# M482SIDv2.net
KiCad netlist of a schematic drawn in EasyEDA
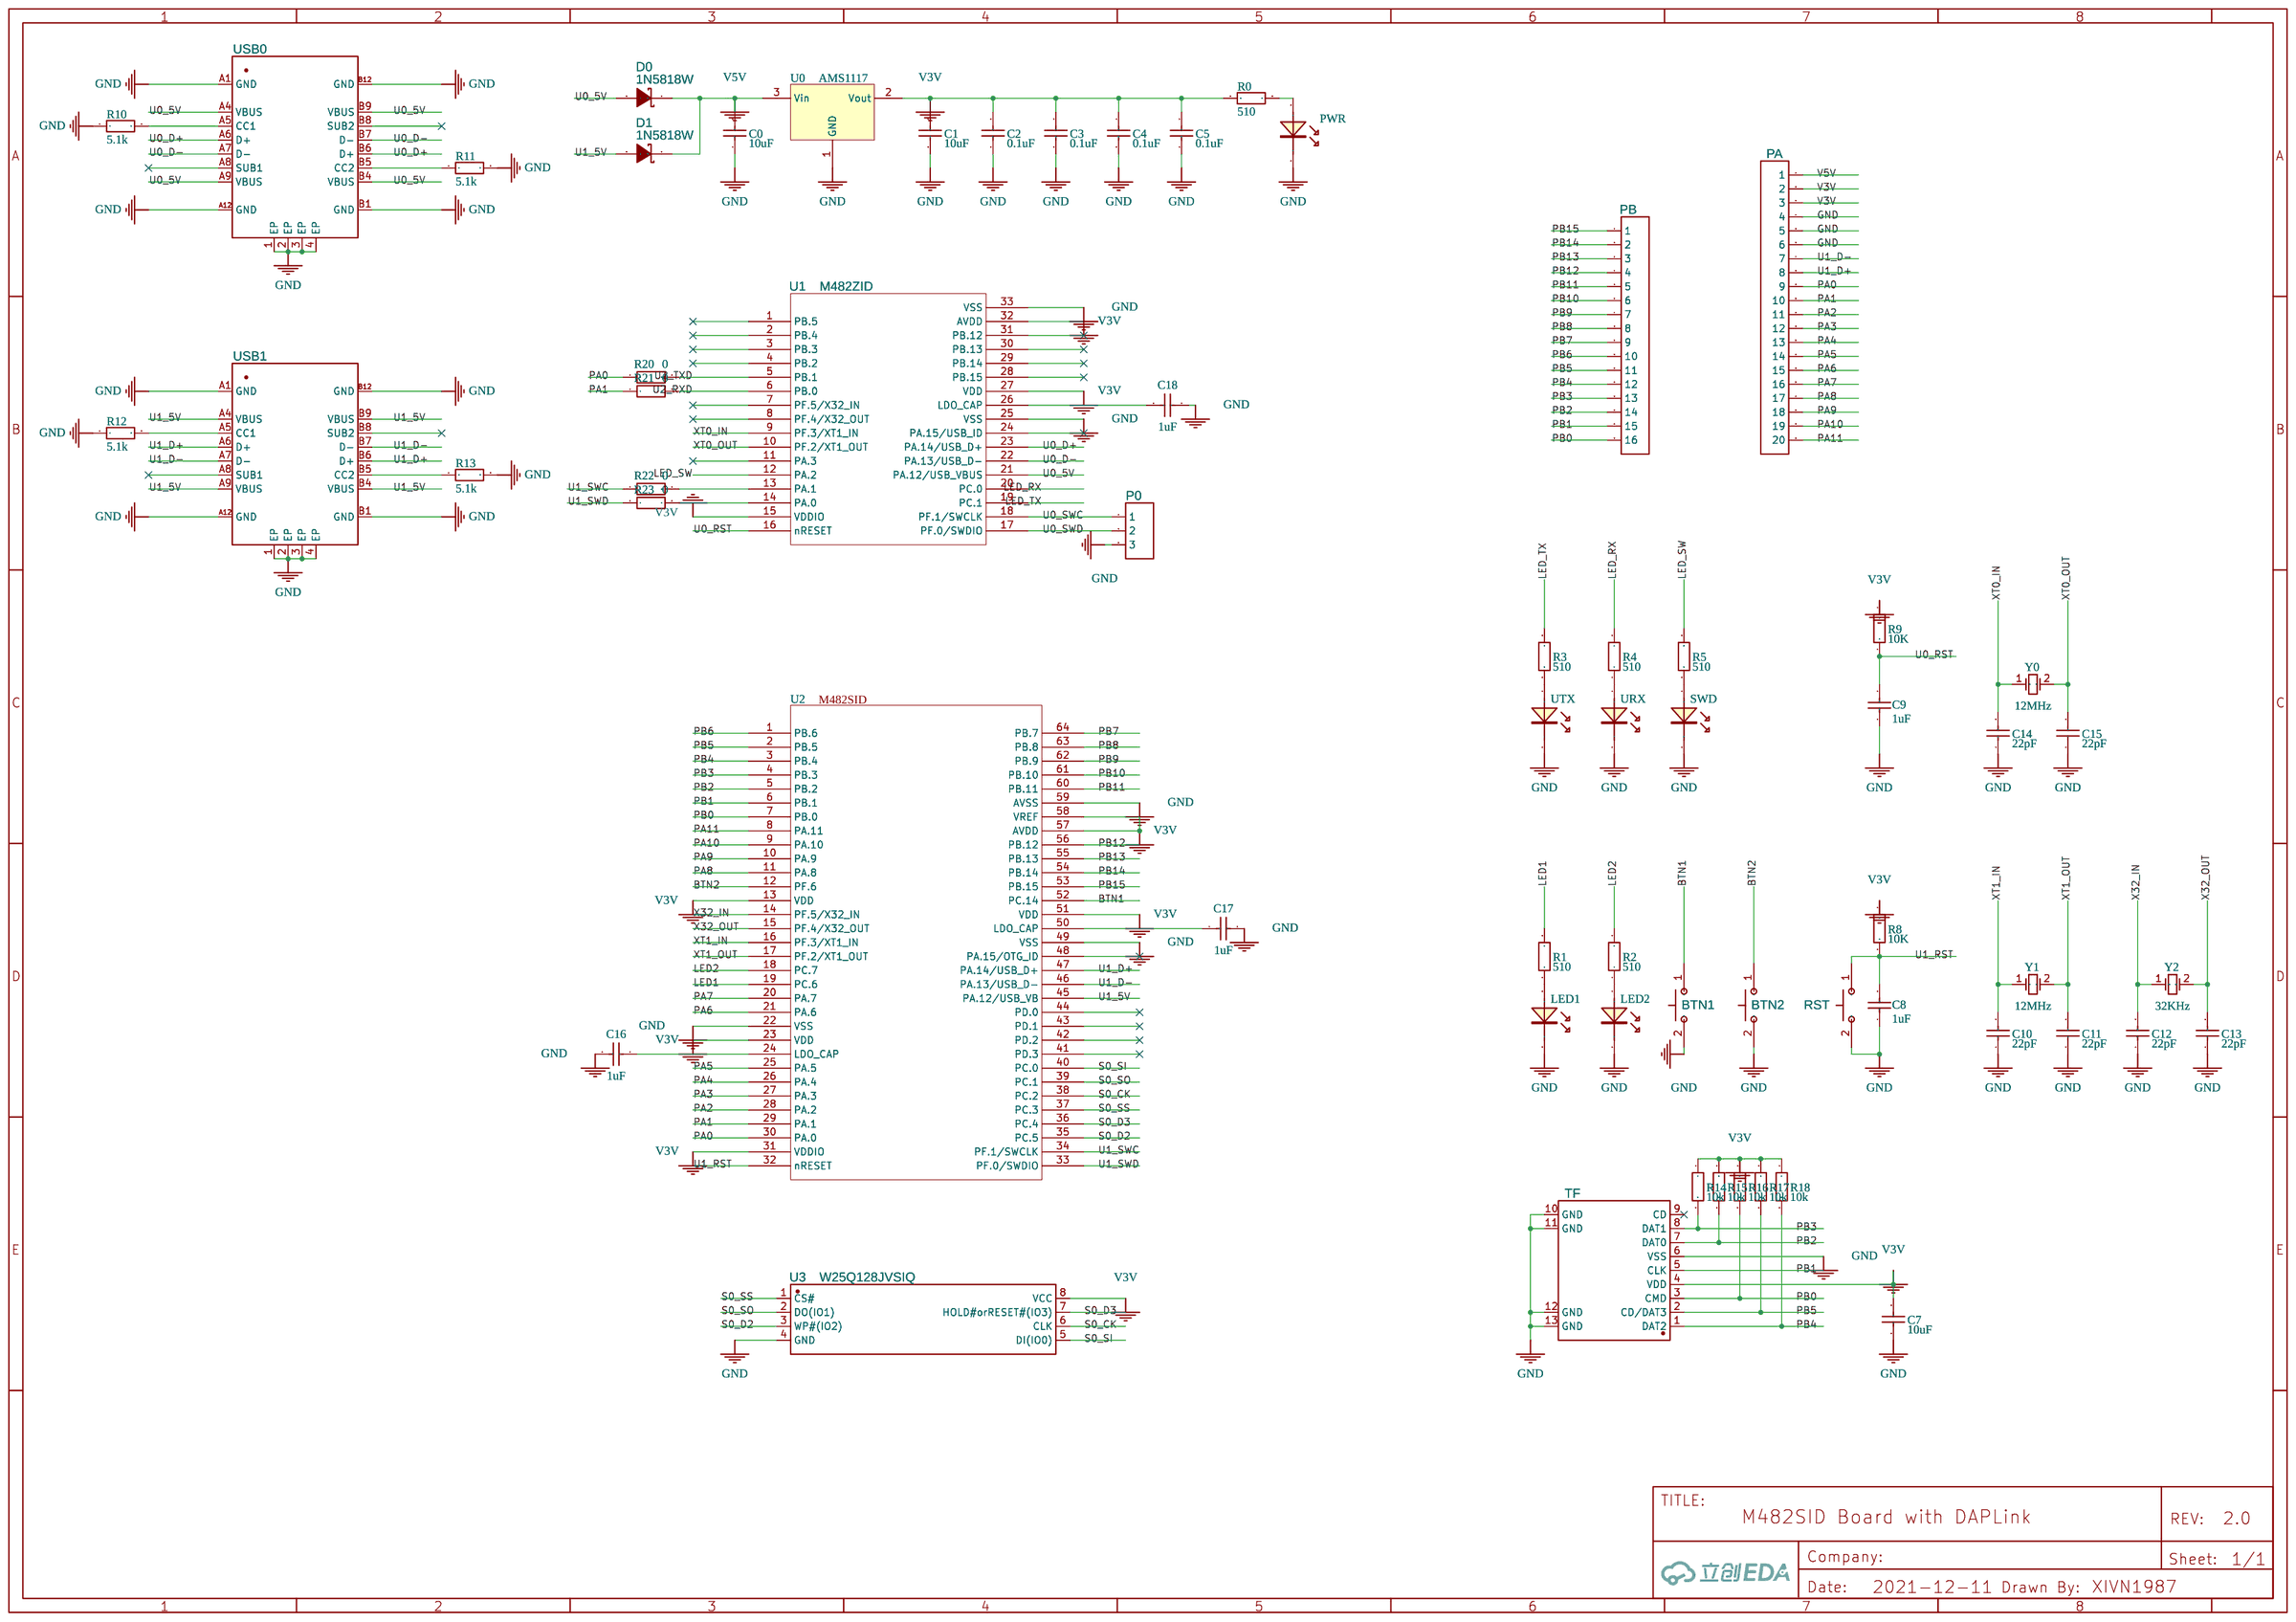
[diagram p0: schematic sheet]

(export (version "E")
  (design (tool "Eeschema 10.0.6"))
  (components
    (comp (ref "BTN1")
      (value "1TS002B-2600-4301")
      (fields (field (name "BOM_Supplier Part") "C318835"))
      (libsource (lib "") (part "1TS002B-2600-4301_1"))
    )
    (comp (ref "BTN2")
      (value "1TS002B-2600-4301")
      (fields (field (name "BOM_Supplier Part") "C318835"))
      (libsource (lib "") (part "1TS002B-2600-4301_1"))
    )
    (comp (ref "C0") (value "10uF") (libsource (lib "") (part "Unknown_510_-710")))
    (comp (ref "C1") (value "10uF") (libsource (lib "") (part "Unknown_650_-710")))
    (comp (ref "C2") (value "0.1uF") (libsource (lib "") (part "Unknown_695_-710")))
    (comp (ref "C3") (value "0.1uF") (libsource (lib "") (part "Unknown_740_-710")))
    (comp (ref "C4") (value "0.1uF") (libsource (lib "") (part "Unknown_785_-710")))
    (comp (ref "C5") (value "0.1uF") (libsource (lib "") (part "Unknown_830_-710")))
    (comp (ref "C7") (value "10uF") (libsource (lib "") (part "Unknown_1340_140")))
    (comp (ref "C8") (value "1uF") (libsource (lib "") (part "Unknown_1330_-85")))
    (comp (ref "C9") (value "1uF") (libsource (lib "") (part "Unknown_1330_-300")))
    (comp (ref "C10") (value "22pF") (libsource (lib "") (part "Unknown_1415_-65")))
    (comp (ref "C11") (value "22pF") (libsource (lib "") (part "Unknown_1465_-65")))
    (comp (ref "C12") (value "22pF") (libsource (lib "") (part "Unknown_1515_-65")))
    (comp (ref "C13") (value "22pF") (libsource (lib "") (part "Unknown_1565_-65")))
    (comp (ref "C14") (value "22pF") (libsource (lib "") (part "Unknown_1415_-280")))
    (comp (ref "C15") (value "22pF") (libsource (lib "") (part "Unknown_1465_-280")))
    (comp (ref "C16") (value "1uF") (libsource (lib "") (part "Unknown_440_-45")))
    (comp (ref "C17") (value "1uF") (libsource (lib "") (part "Unknown_865_-155")))
    (comp (ref "C18") (value "1uF") (libsource (lib "") (part "Unknown_835_-510")))
    (comp (ref "D0")
      (value "1N5818W")
      (fields (field (name "BOM_Supplier Part") "C437955"))
      (libsource (lib "") (part "1N5818W"))
    )
    (comp (ref "D1")
      (value "1N5818W")
      (fields (field (name "BOM_Supplier Part") "C437955"))
      (libsource (lib "") (part "1N5818W"))
    )
    (comp (ref "LED1") (value "NO") (libsource (lib "") (part "Unknown_1100_-105")))
    (comp (ref "LED2") (value "NO") (libsource (lib "") (part "Unknown_1150_-105")))
    (comp (ref "P0")
      (value "HDR-M-2.54_1x3")
      (fields (field (name "BOM_Supplier Part") "C180248"))
      (libsource (lib "") (part "HDR-M-2.54_1x3"))
    )
    (comp (ref "PA")
      (value "HDR-M-2.54_1x20")
      (fields (field (name "BOM_Supplier Part") "C50981"))
      (libsource (lib "") (part "HDR-M-2.54_1x20"))
    )
    (comp (ref "PB")
      (value "HDR-M-2.54_1x16")
      (fields (field (name "BOM_Supplier Part") "C50981"))
      (libsource (lib "") (part "HDR-M-2.54_1x16"))
    )
    (comp (ref "PWR") (value "NO") (libsource (lib "") (part "Unknown_920_-740")))
    (comp (ref "R0") (value "510") (libsource (lib "") (part "Unknown_900_-740")))
    (comp (ref "R1") (value "510") (libsource (lib "") (part "Unknown_1100_-135")))
    (comp (ref "R2") (value "510") (libsource (lib "") (part "Unknown_1150_-135")))
    (comp (ref "R3") (value "510") (libsource (lib "") (part "Unknown_1100_-350")))
    (comp (ref "R4") (value "510") (libsource (lib "") (part "Unknown_1150_-350")))
    (comp (ref "R5") (value "510") (libsource (lib "") (part "Unknown_1200_-350")))
    (comp (ref "R8") (value "10K") (libsource (lib "") (part "Unknown_1340_-135")))
    (comp (ref "R9") (value "10K") (libsource (lib "") (part "Unknown_1340_-350")))
    (comp (ref "R10") (value "5.1k") (libsource (lib "") (part "Unknown_90_-720")))
    (comp (ref "R11") (value "5.1k") (libsource (lib "") (part "Unknown_340_-690")))
    (comp (ref "R12") (value "5.1k") (libsource (lib "") (part "Unknown_90_-500")))
    (comp (ref "R13") (value "5.1k") (libsource (lib "") (part "Unknown_340_-470")))
    (comp (ref "R14") (value "10k") (libsource (lib "") (part "Unknown_1210_50")))
    (comp (ref "R15") (value "10k") (libsource (lib "") (part "Unknown_1225_50")))
    (comp (ref "R16") (value "10k") (libsource (lib "") (part "Unknown_1240_50")))
    (comp (ref "R17") (value "10k") (libsource (lib "") (part "Unknown_1255_50")))
    (comp (ref "R18") (value "10k") (libsource (lib "") (part "Unknown_1270_50")))
    (comp (ref "R20") (value "0") (libsource (lib "") (part "Unknown_470_-540")))
    (comp (ref "R21") (value "0") (libsource (lib "") (part "Unknown_470_-530")))
    (comp (ref "R22") (value "0") (libsource (lib "") (part "Unknown_470_-460")))
    (comp (ref "R23") (value "0") (libsource (lib "") (part "Unknown_470_-450")))
    (comp (ref "RST")
      (value "1TS002B-2600-4301")
      (fields (field (name "BOM_Supplier Part") "C318835"))
      (libsource (lib "") (part "1TS002B-2600-4301"))
    )
    (comp (ref "SWD") (value "NO") (libsource (lib "") (part "Unknown_1200_-320")))
    (comp (ref "TF")
      (value "TF-01A_C2889258")
      (fields (field (name "BOM_Manufacturer Part") "TF-01A") (field (name "BOM_Supplier Part") "C2889258"))
      (libsource (lib "") (part "TF-01A_C2889258"))
    )
    (comp (ref "U0") (value "AMS1117") (libsource (lib "") (part "Unknown_620_-710")))
    (comp (ref "U1") (value "M482ZID") (libsource (lib "") (part "M482ZID")))
    (comp (ref "U2") (value "*") (libsource (lib "") (part "Unknown_560_35")))
    (comp (ref "U3")
      (value "W25Q128JVSIQ")
      (fields (field (name "BOM_Supplier Part") "C113767"))
      (libsource (lib "") (part "W25Q128JVSIQ"))
    )
    (comp (ref "URX") (value "NO") (libsource (lib "") (part "Unknown_1150_-320")))
    (comp (ref "USB0")
      (value "KH-TYPE-C-16P-T")
      (fields (field (name "BOM_Supplier Part") "C709358"))
      (libsource (lib "") (part "KH-TYPE-C-16P-T"))
    )
    (comp (ref "USB1")
      (value "KH-TYPE-C-16P-T")
      (fields (field (name "BOM_Supplier Part") "C709358"))
      (libsource (lib "") (part "KH-TYPE-C-16P-T"))
    )
    (comp (ref "UTX") (value "NO") (libsource (lib "") (part "Unknown_1100_-320")))
    (comp (ref "Y0") (value "12MHz") (libsource (lib "") (part "Unknown_1445_-320")))
    (comp (ref "Y1") (value "12MHz") (libsource (lib "") (part "Unknown_1445_-105")))
    (comp (ref "Y2") (value "32KHz") (libsource (lib "") (part "Unknown_1545_-105")))
  )
  (nets
    (net (code "1") (name "/BTN1") (class "Default")
      (node (ref "BTN1") (pin "1") (pinfunction "A_1") (pintype "unspecified"))
      (node (ref "U2") (pin "52") (pinfunction "PC.14_52") (pintype "unspecified"))
    )
    (net (code "2") (name "/BTN2") (class "Default")
      (node (ref "BTN2") (pin "1") (pinfunction "A_1") (pintype "unspecified"))
      (node (ref "U2") (pin "12") (pinfunction "PF.6_12") (pintype "unspecified"))
    )
    (net (code "3") (name "/LED1") (class "Default")
      (node (ref "R1") (pin "2") (pinfunction "2_2") (pintype "unspecified"))
      (node (ref "U2") (pin "19") (pinfunction "PC.6_19") (pintype "unspecified"))
    )
    (net (code "4") (name "/LED2") (class "Default")
      (node (ref "R2") (pin "2") (pinfunction "2_2") (pintype "unspecified"))
      (node (ref "U2") (pin "18") (pinfunction "PC.7_18") (pintype "unspecified"))
    )
    (net (code "5") (name "/LED_RX") (class "Default")
      (node (ref "R4") (pin "2") (pinfunction "2_2") (pintype "unspecified"))
      (node (ref "U1") (pin "20") (pinfunction "PC.0_20") (pintype "unspecified"))
    )
    (net (code "6") (name "/LED_SW") (class "Default")
      (node (ref "R5") (pin "2") (pinfunction "2_2") (pintype "unspecified"))
      (node (ref "U1") (pin "12") (pinfunction "PA.2_12") (pintype "unspecified"))
    )
    (net (code "7") (name "/LED_TX") (class "Default")
      (node (ref "R3") (pin "2") (pinfunction "2_2") (pintype "unspecified"))
      (node (ref "U1") (pin "19") (pinfunction "PC.1_19") (pintype "unspecified"))
    )
    (net (code "8") (name "/PA0") (class "Default")
      (node (ref "PA") (pin "9") (pinfunction "9_9") (pintype "unspecified"))
      (node (ref "R20") (pin "1") (pinfunction "1_1") (pintype "unspecified"))
      (node (ref "U2") (pin "30") (pinfunction "PA.0_30") (pintype "unspecified"))
    )
    (net (code "9") (name "/PA1") (class "Default")
      (node (ref "PA") (pin "10") (pinfunction "10_10") (pintype "unspecified"))
      (node (ref "R21") (pin "1") (pinfunction "1_1") (pintype "unspecified"))
      (node (ref "U2") (pin "29") (pinfunction "PA.1_29") (pintype "unspecified"))
    )
    (net (code "10") (name "/PA2") (class "Default")
      (node (ref "PA") (pin "11") (pinfunction "11_11") (pintype "unspecified"))
      (node (ref "U2") (pin "28") (pinfunction "PA.2_28") (pintype "unspecified"))
    )
    (net (code "11") (name "/PA3") (class "Default")
      (node (ref "PA") (pin "12") (pinfunction "12_12") (pintype "unspecified"))
      (node (ref "U2") (pin "27") (pinfunction "PA.3_27") (pintype "unspecified"))
    )
    (net (code "12") (name "/PA4") (class "Default")
      (node (ref "PA") (pin "13") (pinfunction "13_13") (pintype "unspecified"))
      (node (ref "U2") (pin "26") (pinfunction "PA.4_26") (pintype "unspecified"))
    )
    (net (code "13") (name "/PA5") (class "Default")
      (node (ref "PA") (pin "14") (pinfunction "14_14") (pintype "unspecified"))
      (node (ref "U2") (pin "25") (pinfunction "PA.5_25") (pintype "unspecified"))
    )
    (net (code "14") (name "/PA6") (class "Default")
      (node (ref "PA") (pin "15") (pinfunction "15_15") (pintype "unspecified"))
      (node (ref "U2") (pin "21") (pinfunction "PA.6_21") (pintype "unspecified"))
    )
    (net (code "15") (name "/PA7") (class "Default")
      (node (ref "PA") (pin "16") (pinfunction "16_16") (pintype "unspecified"))
      (node (ref "U2") (pin "20") (pinfunction "PA.7_20") (pintype "unspecified"))
    )
    (net (code "16") (name "/PA8") (class "Default")
      (node (ref "PA") (pin "17") (pinfunction "17_17") (pintype "unspecified"))
      (node (ref "U2") (pin "11") (pinfunction "PA.8_11") (pintype "unspecified"))
    )
    (net (code "17") (name "/PA9") (class "Default")
      (node (ref "PA") (pin "18") (pinfunction "18_18") (pintype "unspecified"))
      (node (ref "U2") (pin "10") (pinfunction "PA.9_10") (pintype "unspecified"))
    )
    (net (code "18") (name "/PA10") (class "Default")
      (node (ref "PA") (pin "19") (pinfunction "19_19") (pintype "unspecified"))
      (node (ref "U2") (pin "9") (pinfunction "PA.10_9") (pintype "unspecified"))
    )
    (net (code "19") (name "/PA11") (class "Default")
      (node (ref "PA") (pin "20") (pinfunction "20_20") (pintype "unspecified"))
      (node (ref "U2") (pin "8") (pinfunction "PA.11_8") (pintype "unspecified"))
    )
    (net (code "20") (name "/PB0") (class "Default")
      (node (ref "PB") (pin "16") (pinfunction "16_16") (pintype "unspecified"))
      (node (ref "R16") (pin "2") (pinfunction "2_2") (pintype "unspecified"))
      (node (ref "TF") (pin "3") (pinfunction "CMD_3") (pintype "unspecified"))
      (node (ref "U2") (pin "7") (pinfunction "PB.0_7") (pintype "unspecified"))
    )
    (net (code "21") (name "/PB1") (class "Default")
      (node (ref "PB") (pin "15") (pinfunction "15_15") (pintype "unspecified"))
      (node (ref "TF") (pin "5") (pinfunction "CLK_5") (pintype "unspecified"))
      (node (ref "U2") (pin "6") (pinfunction "PB.1_6") (pintype "unspecified"))
    )
    (net (code "22") (name "/PB2") (class "Default")
      (node (ref "PB") (pin "14") (pinfunction "14_14") (pintype "unspecified"))
      (node (ref "R15") (pin "2") (pinfunction "2_2") (pintype "unspecified"))
      (node (ref "TF") (pin "7") (pinfunction "DAT0_7") (pintype "unspecified"))
      (node (ref "U2") (pin "5") (pinfunction "PB.2_5") (pintype "unspecified"))
    )
    (net (code "23") (name "/PB3") (class "Default")
      (node (ref "PB") (pin "13") (pinfunction "13_13") (pintype "unspecified"))
      (node (ref "R14") (pin "2") (pinfunction "2_2") (pintype "unspecified"))
      (node (ref "TF") (pin "8") (pinfunction "DAT1_8") (pintype "unspecified"))
      (node (ref "U2") (pin "4") (pinfunction "PB.3_4") (pintype "unspecified"))
    )
    (net (code "24") (name "/PB4") (class "Default")
      (node (ref "PB") (pin "12") (pinfunction "12_12") (pintype "unspecified"))
      (node (ref "R18") (pin "2") (pinfunction "2_2") (pintype "unspecified"))
      (node (ref "TF") (pin "1") (pinfunction "DAT2_1") (pintype "unspecified"))
      (node (ref "U2") (pin "3") (pinfunction "PB.4_3") (pintype "unspecified"))
    )
    (net (code "25") (name "/PB5") (class "Default")
      (node (ref "PB") (pin "11") (pinfunction "11_11") (pintype "unspecified"))
      (node (ref "R17") (pin "2") (pinfunction "2_2") (pintype "unspecified"))
      (node (ref "TF") (pin "2") (pinfunction "CD/DAT3_2") (pintype "unspecified"))
      (node (ref "U2") (pin "2") (pinfunction "PB.5_2") (pintype "unspecified"))
    )
    (net (code "26") (name "/PB6") (class "Default")
      (node (ref "PB") (pin "10") (pinfunction "10_10") (pintype "unspecified"))
      (node (ref "U2") (pin "1") (pinfunction "PB.6_1") (pintype "unspecified"))
    )
    (net (code "27") (name "/PB7") (class "Default")
      (node (ref "PB") (pin "9") (pinfunction "9_9") (pintype "unspecified"))
      (node (ref "U2") (pin "64") (pinfunction "PB.7_64") (pintype "unspecified"))
    )
    (net (code "28") (name "/PB8") (class "Default")
      (node (ref "PB") (pin "8") (pinfunction "8_8") (pintype "unspecified"))
      (node (ref "U2") (pin "63") (pinfunction "PB.8_63") (pintype "unspecified"))
    )
    (net (code "29") (name "/PB9") (class "Default")
      (node (ref "PB") (pin "7") (pinfunction "7_7") (pintype "unspecified"))
      (node (ref "U2") (pin "62") (pinfunction "PB.9_62") (pintype "unspecified"))
    )
    (net (code "30") (name "/PB10") (class "Default")
      (node (ref "PB") (pin "6") (pinfunction "6_6") (pintype "unspecified"))
      (node (ref "U2") (pin "61") (pinfunction "PB.10_61") (pintype "unspecified"))
    )
    (net (code "31") (name "/PB11") (class "Default")
      (node (ref "PB") (pin "5") (pinfunction "5_5") (pintype "unspecified"))
      (node (ref "U2") (pin "60") (pinfunction "PB.11_60") (pintype "unspecified"))
    )
    (net (code "32") (name "/PB12") (class "Default")
      (node (ref "PB") (pin "4") (pinfunction "4_4") (pintype "unspecified"))
      (node (ref "U2") (pin "56") (pinfunction "PB.12_56") (pintype "unspecified"))
    )
    (net (code "33") (name "/PB13") (class "Default")
      (node (ref "PB") (pin "3") (pinfunction "3_3") (pintype "unspecified"))
      (node (ref "U2") (pin "55") (pinfunction "PB.13_55") (pintype "unspecified"))
    )
    (net (code "34") (name "/PB14") (class "Default")
      (node (ref "PB") (pin "2") (pinfunction "2_2") (pintype "unspecified"))
      (node (ref "U2") (pin "54") (pinfunction "PB.14_54") (pintype "unspecified"))
    )
    (net (code "35") (name "/PB15") (class "Default")
      (node (ref "PB") (pin "1") (pinfunction "1_1") (pintype "unspecified"))
      (node (ref "U2") (pin "53") (pinfunction "PB.15_53") (pintype "unspecified"))
    )
    (net (code "36") (name "/S0_CK") (class "Default")
      (node (ref "U2") (pin "38") (pinfunction "PC.2_38") (pintype "unspecified"))
      (node (ref "U3") (pin "6") (pinfunction "CLK_6") (pintype "unspecified"))
    )
    (net (code "37") (name "/S0_D2") (class "Default")
      (node (ref "U2") (pin "35") (pinfunction "PC.5_35") (pintype "unspecified"))
      (node (ref "U3") (pin "3") (pinfunction "WP#(IO2)_3") (pintype "unspecified"))
    )
    (net (code "38") (name "/S0_D3") (class "Default")
      (node (ref "U2") (pin "36") (pinfunction "PC.4_36") (pintype "unspecified"))
      (node (ref "U3") (pin "7") (pinfunction "HOLD#orRESET#(IO3)_7") (pintype "unspecified"))
    )
    (net (code "39") (name "/S0_SI") (class "Default")
      (node (ref "U2") (pin "40") (pinfunction "PC.0_40") (pintype "unspecified"))
      (node (ref "U3") (pin "5") (pinfunction "DI(IO0)_5") (pintype "unspecified"))
    )
    (net (code "40") (name "/S0_SO") (class "Default")
      (node (ref "U2") (pin "39") (pinfunction "PC.1_39") (pintype "unspecified"))
      (node (ref "U3") (pin "2") (pinfunction "DO(IO1)_2") (pintype "unspecified"))
    )
    (net (code "41") (name "/S0_SS") (class "Default")
      (node (ref "U2") (pin "37") (pinfunction "PC.3_37") (pintype "unspecified"))
      (node (ref "U3") (pin "1") (pinfunction "CS#_1") (pintype "unspecified"))
    )
    (net (code "42") (name "/U0_5V") (class "Default")
      (node (ref "D0") (pin "2") (pinfunction "A_2") (pintype "unspecified"))
      (node (ref "U1") (pin "21") (pinfunction "PA.12/USB_VBUS_21") (pintype "unspecified"))
      (node (ref "USB0") (pin "A4") (pinfunction "VBUS_A4") (pintype "unspecified"))
      (node (ref "USB0") (pin "A9") (pinfunction "VBUS_A9") (pintype "unspecified"))
      (node (ref "USB0") (pin "B4") (pinfunction "VBUS_B4") (pintype "unspecified"))
      (node (ref "USB0") (pin "B9") (pinfunction "VBUS_B9") (pintype "unspecified"))
    )
    (net (code "43") (name "/U0_D+") (class "Default")
      (node (ref "U1") (pin "23") (pinfunction "PA.14/USB_D+_23") (pintype "unspecified"))
      (node (ref "USB0") (pin "A6") (pinfunction "D+_A6") (pintype "unspecified"))
      (node (ref "USB0") (pin "B6") (pinfunction "D+_B6") (pintype "unspecified"))
    )
    (net (code "44") (name "/U0_D-") (class "Default")
      (node (ref "U1") (pin "22") (pinfunction "PA.13/USB_D-_22") (pintype "unspecified"))
      (node (ref "USB0") (pin "A7") (pinfunction "D-_A7") (pintype "unspecified"))
      (node (ref "USB0") (pin "B7") (pinfunction "D-_B7") (pintype "unspecified"))
    )
    (net (code "45") (name "/U0_RST") (class "Default")
      (node (ref "C9") (pin "2") (pinfunction "2_2") (pintype "unspecified"))
      (node (ref "R9") (pin "2") (pinfunction "2_2") (pintype "unspecified"))
      (node (ref "U1") (pin "16") (pinfunction "nRESET_16") (pintype "unspecified"))
    )
    (net (code "46") (name "/U0_SWC") (class "Default")
      (node (ref "P0") (pin "1") (pinfunction "1_1") (pintype "input"))
      (node (ref "U1") (pin "18") (pinfunction "PF.1/SWCLK_18") (pintype "unspecified"))
    )
    (net (code "47") (name "/U0_SWD") (class "Default")
      (node (ref "P0") (pin "2") (pinfunction "2_2") (pintype "input"))
      (node (ref "U1") (pin "17") (pinfunction "PF.0/SWDIO_17") (pintype "unspecified"))
    )
    (net (code "48") (name "/U1_5V") (class "Default")
      (node (ref "D1") (pin "2") (pinfunction "A_2") (pintype "unspecified"))
      (node (ref "U2") (pin "45") (pinfunction "PA.12/USB_VB_45") (pintype "unspecified"))
      (node (ref "USB1") (pin "A4") (pinfunction "VBUS_A4") (pintype "unspecified"))
      (node (ref "USB1") (pin "A9") (pinfunction "VBUS_A9") (pintype "unspecified"))
      (node (ref "USB1") (pin "B4") (pinfunction "VBUS_B4") (pintype "unspecified"))
      (node (ref "USB1") (pin "B9") (pinfunction "VBUS_B9") (pintype "unspecified"))
    )
    (net (code "49") (name "/U1_D+") (class "Default")
      (node (ref "PA") (pin "8") (pinfunction "8_8") (pintype "unspecified"))
      (node (ref "U2") (pin "47") (pinfunction "PA.14/USB_D+_47") (pintype "unspecified"))
      (node (ref "USB1") (pin "A6") (pinfunction "D+_A6") (pintype "unspecified"))
      (node (ref "USB1") (pin "B6") (pinfunction "D+_B6") (pintype "unspecified"))
    )
    (net (code "50") (name "/U1_D-") (class "Default")
      (node (ref "PA") (pin "7") (pinfunction "7_7") (pintype "unspecified"))
      (node (ref "U2") (pin "46") (pinfunction "PA.13/USB_D-_46") (pintype "unspecified"))
      (node (ref "USB1") (pin "A7") (pinfunction "D-_A7") (pintype "unspecified"))
      (node (ref "USB1") (pin "B7") (pinfunction "D-_B7") (pintype "unspecified"))
    )
    (net (code "51") (name "/U1_RST") (class "Default")
      (node (ref "C8") (pin "2") (pinfunction "2_2") (pintype "unspecified"))
      (node (ref "R8") (pin "2") (pinfunction "2_2") (pintype "unspecified"))
      (node (ref "RST") (pin "1") (pinfunction "A_1") (pintype "unspecified"))
      (node (ref "U2") (pin "32") (pinfunction "nRESET_32") (pintype "unspecified"))
    )
    (net (code "52") (name "/U1_SWC") (class "Default")
      (node (ref "R22") (pin "1") (pinfunction "1_1") (pintype "unspecified"))
      (node (ref "U2") (pin "34") (pinfunction "PF.1/SWCLK_34") (pintype "unspecified"))
    )
    (net (code "53") (name "/U1_SWD") (class "Default")
      (node (ref "R23") (pin "1") (pinfunction "1_1") (pintype "unspecified"))
      (node (ref "U2") (pin "33") (pinfunction "PF.0/SWDIO_33") (pintype "unspecified"))
    )
    (net (code "54") (name "/U2_RXD") (class "Default")
      (node (ref "R21") (pin "2") (pinfunction "2_2") (pintype "unspecified"))
      (node (ref "U1") (pin "6") (pinfunction "PB.0_6") (pintype "unspecified"))
    )
    (net (code "55") (name "/U2_TXD") (class "Default")
      (node (ref "R20") (pin "2") (pinfunction "2_2") (pintype "unspecified"))
      (node (ref "U1") (pin "5") (pinfunction "PB.1_5") (pintype "unspecified"))
    )
    (net (code "56") (name "/X32_IN") (class "Default")
      (node (ref "C12") (pin "2") (pinfunction "2_2") (pintype "unspecified"))
      (node (ref "U2") (pin "14") (pinfunction "PF.5/X32_IN_14") (pintype "unspecified"))
      (node (ref "Y2") (pin "1") (pinfunction "OSC1_1") (pintype "unspecified"))
    )
    (net (code "57") (name "/X32_OUT") (class "Default")
      (node (ref "C13") (pin "2") (pinfunction "2_2") (pintype "unspecified"))
      (node (ref "U2") (pin "15") (pinfunction "PF.4/X32_OUT_15") (pintype "unspecified"))
      (node (ref "Y2") (pin "2") (pinfunction "OSC2_2") (pintype "unspecified"))
    )
    (net (code "58") (name "/XT0_IN") (class "Default")
      (node (ref "C14") (pin "2") (pinfunction "2_2") (pintype "unspecified"))
      (node (ref "U1") (pin "9") (pinfunction "PF.3/XT1_IN_9") (pintype "unspecified"))
      (node (ref "Y0") (pin "1") (pinfunction "OSC1_1") (pintype "unspecified"))
    )
    (net (code "59") (name "/XT0_OUT") (class "Default")
      (node (ref "C15") (pin "2") (pinfunction "2_2") (pintype "unspecified"))
      (node (ref "U1") (pin "10") (pinfunction "PF.2/XT1_OUT_10") (pintype "unspecified"))
      (node (ref "Y0") (pin "2") (pinfunction "OSC2_2") (pintype "unspecified"))
    )
    (net (code "60") (name "/XT1_IN") (class "Default")
      (node (ref "C10") (pin "2") (pinfunction "2_2") (pintype "unspecified"))
      (node (ref "U2") (pin "16") (pinfunction "PF.3/XT1_IN_16") (pintype "unspecified"))
      (node (ref "Y1") (pin "1") (pinfunction "OSC1_1") (pintype "unspecified"))
    )
    (net (code "61") (name "/XT1_OUT") (class "Default")
      (node (ref "C11") (pin "2") (pinfunction "2_2") (pintype "unspecified"))
      (node (ref "U2") (pin "17") (pinfunction "PF.2/XT1_OUT_17") (pintype "unspecified"))
      (node (ref "Y1") (pin "2") (pinfunction "OSC2_2") (pintype "unspecified"))
    )
    (net (code "62") (name "GND") (class "Default")
      (node (ref "BTN1") (pin "2") (pinfunction "B_2") (pintype "unspecified"))
      (node (ref "BTN2") (pin "2") (pinfunction "B_2") (pintype "unspecified"))
      (node (ref "C0") (pin "1") (pinfunction "1_1") (pintype "unspecified"))
      (node (ref "C1") (pin "1") (pinfunction "1_1") (pintype "unspecified"))
      (node (ref "C10") (pin "1") (pinfunction "1_1") (pintype "unspecified"))
      (node (ref "C11") (pin "1") (pinfunction "1_1") (pintype "unspecified"))
      (node (ref "C12") (pin "1") (pinfunction "1_1") (pintype "unspecified"))
      (node (ref "C13") (pin "1") (pinfunction "1_1") (pintype "unspecified"))
      (node (ref "C14") (pin "1") (pinfunction "1_1") (pintype "unspecified"))
      (node (ref "C15") (pin "1") (pinfunction "1_1") (pintype "unspecified"))
      (node (ref "C16") (pin "2") (pinfunction "2_2") (pintype "unspecified"))
      (node (ref "C17") (pin "2") (pinfunction "2_2") (pintype "unspecified"))
      (node (ref "C18") (pin "1") (pinfunction "1_1") (pintype "unspecified"))
      (node (ref "C2") (pin "1") (pinfunction "1_1") (pintype "unspecified"))
      (node (ref "C3") (pin "1") (pinfunction "1_1") (pintype "unspecified"))
      (node (ref "C4") (pin "1") (pinfunction "1_1") (pintype "unspecified"))
      (node (ref "C5") (pin "1") (pinfunction "1_1") (pintype "unspecified"))
      (node (ref "C7") (pin "1") (pinfunction "1_1") (pintype "unspecified"))
      (node (ref "C8") (pin "1") (pinfunction "1_1") (pintype "unspecified"))
      (node (ref "C9") (pin "1") (pinfunction "1_1") (pintype "unspecified"))
      (node (ref "LED1") (pin "2") (pinfunction "K_2") (pintype "unspecified"))
      (node (ref "LED2") (pin "2") (pinfunction "K_2") (pintype "unspecified"))
      (node (ref "P0") (pin "3") (pinfunction "3_3") (pintype "input"))
      (node (ref "PA") (pin "4") (pinfunction "4_4") (pintype "unspecified"))
      (node (ref "PA") (pin "5") (pinfunction "5_5") (pintype "unspecified"))
      (node (ref "PA") (pin "6") (pinfunction "6_6") (pintype "unspecified"))
      (node (ref "PWR") (pin "2") (pinfunction "K_2") (pintype "unspecified"))
      (node (ref "R10") (pin "1") (pinfunction "1_1") (pintype "unspecified"))
      (node (ref "R11") (pin "2") (pinfunction "2_2") (pintype "unspecified"))
      (node (ref "R12") (pin "1") (pinfunction "1_1") (pintype "unspecified"))
      (node (ref "R13") (pin "2") (pinfunction "2_2") (pintype "unspecified"))
      (node (ref "RST") (pin "2") (pinfunction "B_2") (pintype "unspecified"))
      (node (ref "SWD") (pin "2") (pinfunction "K_2") (pintype "unspecified"))
      (node (ref "TF") (pin "10") (pinfunction "GND_10") (pintype "unspecified"))
      (node (ref "TF") (pin "11") (pinfunction "GND_11") (pintype "unspecified"))
      (node (ref "TF") (pin "12") (pinfunction "GND_12") (pintype "unspecified"))
      (node (ref "TF") (pin "13") (pinfunction "GND_13") (pintype "unspecified"))
      (node (ref "TF") (pin "6") (pinfunction "VSS_6") (pintype "unspecified"))
      (node (ref "U0") (pin "1") (pinfunction "GND_1") (pintype "unspecified"))
      (node (ref "U1") (pin "25") (pinfunction "VSS_25") (pintype "unspecified"))
      (node (ref "U1") (pin "33") (pinfunction "VSS_33") (pintype "unspecified"))
      (node (ref "U2") (pin "22") (pinfunction "VSS_22") (pintype "unspecified"))
      (node (ref "U2") (pin "49") (pinfunction "VSS_49") (pintype "unspecified"))
      (node (ref "U2") (pin "59") (pinfunction "AVSS_59") (pintype "unspecified"))
      (node (ref "U3") (pin "4") (pinfunction "GND_4") (pintype "unspecified"))
      (node (ref "URX") (pin "2") (pinfunction "K_2") (pintype "unspecified"))
      (node (ref "USB0") (pin "1") (pinfunction "EP_1") (pintype "unspecified"))
      (node (ref "USB0") (pin "2") (pinfunction "EP_2") (pintype "unspecified"))
      (node (ref "USB0") (pin "3") (pinfunction "EP_3") (pintype "unspecified"))
      (node (ref "USB0") (pin "4") (pinfunction "EP_4") (pintype "unspecified"))
      (node (ref "USB0") (pin "A1") (pinfunction "GND_A1") (pintype "unspecified"))
      (node (ref "USB0") (pin "A12") (pinfunction "GND_A12") (pintype "unspecified"))
      (node (ref "USB0") (pin "B1") (pinfunction "GND_B1") (pintype "unspecified"))
      (node (ref "USB0") (pin "B12") (pinfunction "GND_B12") (pintype "unspecified"))
      (node (ref "USB1") (pin "1") (pinfunction "EP_1") (pintype "unspecified"))
      (node (ref "USB1") (pin "2") (pinfunction "EP_2") (pintype "unspecified"))
      (node (ref "USB1") (pin "3") (pinfunction "EP_3") (pintype "unspecified"))
      (node (ref "USB1") (pin "4") (pinfunction "EP_4") (pintype "unspecified"))
      (node (ref "USB1") (pin "A1") (pinfunction "GND_A1") (pintype "unspecified"))
      (node (ref "USB1") (pin "A12") (pinfunction "GND_A12") (pintype "unspecified"))
      (node (ref "USB1") (pin "B1") (pinfunction "GND_B1") (pintype "unspecified"))
      (node (ref "USB1") (pin "B12") (pinfunction "GND_B12") (pintype "unspecified"))
      (node (ref "UTX") (pin "2") (pinfunction "K_2") (pintype "unspecified"))
    )
    (net (code "63") (name "Net-(C16-Pad1)") (class "Default")
      (node (ref "C16") (pin "1") (pinfunction "1_1") (pintype "unspecified"))
      (node (ref "U2") (pin "24") (pinfunction "LDO_CAP_24") (pintype "unspecified"))
    )
    (net (code "64") (name "Net-(C17-Pad1)") (class "Default")
      (node (ref "C17") (pin "1") (pinfunction "1_1") (pintype "unspecified"))
      (node (ref "U2") (pin "50") (pinfunction "LDO_CAP_50") (pintype "unspecified"))
    )
    (net (code "65") (name "Net-(LED1-A)") (class "Default")
      (node (ref "LED1") (pin "1") (pinfunction "A_1") (pintype "unspecified"))
      (node (ref "R1") (pin "1") (pinfunction "1_1") (pintype "unspecified"))
    )
    (net (code "66") (name "Net-(LED2-A)") (class "Default")
      (node (ref "LED2") (pin "1") (pinfunction "A_1") (pintype "unspecified"))
      (node (ref "R2") (pin "1") (pinfunction "1_1") (pintype "unspecified"))
    )
    (net (code "67") (name "Net-(PWR-A)") (class "Default")
      (node (ref "PWR") (pin "1") (pinfunction "A_1") (pintype "unspecified"))
      (node (ref "R0") (pin "2") (pinfunction "2_2") (pintype "unspecified"))
    )
    (net (code "68") (name "Net-(SWD-A)") (class "Default")
      (node (ref "R5") (pin "1") (pinfunction "1_1") (pintype "unspecified"))
      (node (ref "SWD") (pin "1") (pinfunction "A_1") (pintype "unspecified"))
    )
    (net (code "69") (name "Net-(U1-LDO_CAP)") (class "Default")
      (node (ref "C18") (pin "2") (pinfunction "2_2") (pintype "unspecified"))
      (node (ref "U1") (pin "26") (pinfunction "LDO_CAP_26") (pintype "unspecified"))
    )
    (net (code "70") (name "Net-(U1-PA.0)") (class "Default")
      (node (ref "R23") (pin "2") (pinfunction "2_2") (pintype "unspecified"))
      (node (ref "U1") (pin "14") (pinfunction "PA.0_14") (pintype "unspecified"))
    )
    (net (code "71") (name "Net-(U1-PA.1)") (class "Default")
      (node (ref "R22") (pin "2") (pinfunction "2_2") (pintype "unspecified"))
      (node (ref "U1") (pin "13") (pinfunction "PA.1_13") (pintype "unspecified"))
    )
    (net (code "72") (name "Net-(URX-A)") (class "Default")
      (node (ref "R4") (pin "1") (pinfunction "1_1") (pintype "unspecified"))
      (node (ref "URX") (pin "1") (pinfunction "A_1") (pintype "unspecified"))
    )
    (net (code "73") (name "Net-(USB0-CC1)") (class "Default")
      (node (ref "R10") (pin "2") (pinfunction "2_2") (pintype "unspecified"))
      (node (ref "USB0") (pin "A5") (pinfunction "CC1_A5") (pintype "unspecified"))
    )
    (net (code "74") (name "Net-(USB0-CC2)") (class "Default")
      (node (ref "R11") (pin "1") (pinfunction "1_1") (pintype "unspecified"))
      (node (ref "USB0") (pin "B5") (pinfunction "CC2_B5") (pintype "unspecified"))
    )
    (net (code "75") (name "Net-(USB1-CC1)") (class "Default")
      (node (ref "R12") (pin "2") (pinfunction "2_2") (pintype "unspecified"))
      (node (ref "USB1") (pin "A5") (pinfunction "CC1_A5") (pintype "unspecified"))
    )
    (net (code "76") (name "Net-(USB1-CC2)") (class "Default")
      (node (ref "R13") (pin "1") (pinfunction "1_1") (pintype "unspecified"))
      (node (ref "USB1") (pin "B5") (pinfunction "CC2_B5") (pintype "unspecified"))
    )
    (net (code "77") (name "Net-(UTX-A)") (class "Default")
      (node (ref "R3") (pin "1") (pinfunction "1_1") (pintype "unspecified"))
      (node (ref "UTX") (pin "1") (pinfunction "A_1") (pintype "unspecified"))
    )
    (net (code "78") (name "V3V") (class "Default")
      (node (ref "C1") (pin "2") (pinfunction "2_2") (pintype "unspecified"))
      (node (ref "C2") (pin "2") (pinfunction "2_2") (pintype "unspecified"))
      (node (ref "C3") (pin "2") (pinfunction "2_2") (pintype "unspecified"))
      (node (ref "C4") (pin "2") (pinfunction "2_2") (pintype "unspecified"))
      (node (ref "C5") (pin "2") (pinfunction "2_2") (pintype "unspecified"))
      (node (ref "C7") (pin "2") (pinfunction "2_2") (pintype "unspecified"))
      (node (ref "PA") (pin "2") (pinfunction "2_2") (pintype "unspecified"))
      (node (ref "PA") (pin "3") (pinfunction "3_3") (pintype "unspecified"))
      (node (ref "R0") (pin "1") (pinfunction "1_1") (pintype "unspecified"))
      (node (ref "R14") (pin "1") (pinfunction "1_1") (pintype "unspecified"))
      (node (ref "R15") (pin "1") (pinfunction "1_1") (pintype "unspecified"))
      (node (ref "R16") (pin "1") (pinfunction "1_1") (pintype "unspecified"))
      (node (ref "R17") (pin "1") (pinfunction "1_1") (pintype "unspecified"))
      (node (ref "R18") (pin "1") (pinfunction "1_1") (pintype "unspecified"))
      (node (ref "R8") (pin "1") (pinfunction "1_1") (pintype "unspecified"))
      (node (ref "R9") (pin "1") (pinfunction "1_1") (pintype "unspecified"))
      (node (ref "TF") (pin "4") (pinfunction "VDD_4") (pintype "unspecified"))
      (node (ref "U0") (pin "2") (pinfunction "Vout_2") (pintype "unspecified"))
      (node (ref "U1") (pin "15") (pinfunction "VDDIO_15") (pintype "unspecified"))
      (node (ref "U1") (pin "27") (pinfunction "VDD_27") (pintype "unspecified"))
      (node (ref "U1") (pin "32") (pinfunction "AVDD_32") (pintype "unspecified"))
      (node (ref "U2") (pin "13") (pinfunction "VDD_13") (pintype "unspecified"))
      (node (ref "U2") (pin "23") (pinfunction "VDD_23") (pintype "unspecified"))
      (node (ref "U2") (pin "31") (pinfunction "VDDIO_31") (pintype "unspecified"))
      (node (ref "U2") (pin "51") (pinfunction "VDD_51") (pintype "unspecified"))
      (node (ref "U2") (pin "57") (pinfunction "AVDD_57") (pintype "unspecified"))
      (node (ref "U2") (pin "58") (pinfunction "VREF_58") (pintype "unspecified"))
      (node (ref "U3") (pin "8") (pinfunction "VCC_8") (pintype "unspecified"))
    )
    (net (code "79") (name "V5V") (class "Default")
      (node (ref "C0") (pin "2") (pinfunction "2_2") (pintype "unspecified"))
      (node (ref "D0") (pin "1") (pinfunction "C_1") (pintype "unspecified"))
      (node (ref "D1") (pin "1") (pinfunction "C_1") (pintype "unspecified"))
      (node (ref "PA") (pin "1") (pinfunction "1_1") (pintype "unspecified"))
      (node (ref "U0") (pin "3") (pinfunction "Vin_3") (pintype "unspecified"))
    )
    (net (code "80") (name "unconnected-(TF-CD-Pad9)") (class "Default")
      (node (ref "TF") (pin "9") (pinfunction "CD_9") (pintype "unspecified+no_connect"))
    )
    (net (code "81") (name "unconnected-(U1-PA.3-Pad11)") (class "Default")
      (node (ref "U1") (pin "11") (pinfunction "PA.3_11") (pintype "unspecified+no_connect"))
    )
    (net (code "82") (name "unconnected-(U1-PA.15{slash}USB_ID-Pad24)") (class "Default")
      (node (ref "U1") (pin "24") (pinfunction "PA.15/USB_ID_24") (pintype "unspecified+no_connect"))
    )
    (net (code "83") (name "unconnected-(U1-PB.2-Pad4)") (class "Default")
      (node (ref "U1") (pin "4") (pinfunction "PB.2_4") (pintype "unspecified+no_connect"))
    )
    (net (code "84") (name "unconnected-(U1-PB.3-Pad3)") (class "Default")
      (node (ref "U1") (pin "3") (pinfunction "PB.3_3") (pintype "unspecified+no_connect"))
    )
    (net (code "85") (name "unconnected-(U1-PB.4-Pad2)") (class "Default")
      (node (ref "U1") (pin "2") (pinfunction "PB.4_2") (pintype "unspecified+no_connect"))
    )
    (net (code "86") (name "unconnected-(U1-PB.5-Pad1)") (class "Default")
      (node (ref "U1") (pin "1") (pinfunction "PB.5_1") (pintype "unspecified+no_connect"))
    )
    (net (code "87") (name "unconnected-(U1-PB.12-Pad31)") (class "Default")
      (node (ref "U1") (pin "31") (pinfunction "PB.12_31") (pintype "unspecified+no_connect"))
    )
    (net (code "88") (name "unconnected-(U1-PB.13-Pad30)") (class "Default")
      (node (ref "U1") (pin "30") (pinfunction "PB.13_30") (pintype "unspecified+no_connect"))
    )
    (net (code "89") (name "unconnected-(U1-PB.14-Pad29)") (class "Default")
      (node (ref "U1") (pin "29") (pinfunction "PB.14_29") (pintype "unspecified+no_connect"))
    )
    (net (code "90") (name "unconnected-(U1-PB.15-Pad28)") (class "Default")
      (node (ref "U1") (pin "28") (pinfunction "PB.15_28") (pintype "unspecified+no_connect"))
    )
    (net (code "91") (name "unconnected-(U1-PF.4{slash}X32_OUT-Pad8)") (class "Default")
      (node (ref "U1") (pin "8") (pinfunction "PF.4/X32_OUT_8") (pintype "unspecified+no_connect"))
    )
    (net (code "92") (name "unconnected-(U1-PF.5{slash}X32_IN-Pad7)") (class "Default")
      (node (ref "U1") (pin "7") (pinfunction "PF.5/X32_IN_7") (pintype "unspecified+no_connect"))
    )
    (net (code "93") (name "unconnected-(U2-PA.15{slash}OTG_ID-Pad48)") (class "Default")
      (node (ref "U2") (pin "48") (pinfunction "PA.15/OTG_ID_48") (pintype "unspecified+no_connect"))
    )
    (net (code "94") (name "unconnected-(U2-PD.0-Pad44)") (class "Default")
      (node (ref "U2") (pin "44") (pinfunction "PD.0_44") (pintype "unspecified+no_connect"))
    )
    (net (code "95") (name "unconnected-(U2-PD.1-Pad43)") (class "Default")
      (node (ref "U2") (pin "43") (pinfunction "PD.1_43") (pintype "unspecified+no_connect"))
    )
    (net (code "96") (name "unconnected-(U2-PD.2-Pad42)") (class "Default")
      (node (ref "U2") (pin "42") (pinfunction "PD.2_42") (pintype "unspecified+no_connect"))
    )
    (net (code "97") (name "unconnected-(U2-PD.3-Pad41)") (class "Default")
      (node (ref "U2") (pin "41") (pinfunction "PD.3_41") (pintype "unspecified+no_connect"))
    )
    (net (code "98") (name "unconnected-(USB0-SUB1-PadA8)") (class "Default")
      (node (ref "USB0") (pin "A8") (pinfunction "SUB1_A8") (pintype "unspecified+no_connect"))
    )
    (net (code "99") (name "unconnected-(USB0-SUB2-PadB8)") (class "Default")
      (node (ref "USB0") (pin "B8") (pinfunction "SUB2_B8") (pintype "unspecified+no_connect"))
    )
    (net (code "100") (name "unconnected-(USB1-SUB1-PadA8)") (class "Default")
      (node (ref "USB1") (pin "A8") (pinfunction "SUB1_A8") (pintype "unspecified+no_connect"))
    )
    (net (code "101") (name "unconnected-(USB1-SUB2-PadB8)") (class "Default")
      (node (ref "USB1") (pin "B8") (pinfunction "SUB2_B8") (pintype "unspecified+no_connect"))
    )
  )
)
